# Connector_LV.net
KiCad netlist of a schematic drawn in Altium Designer
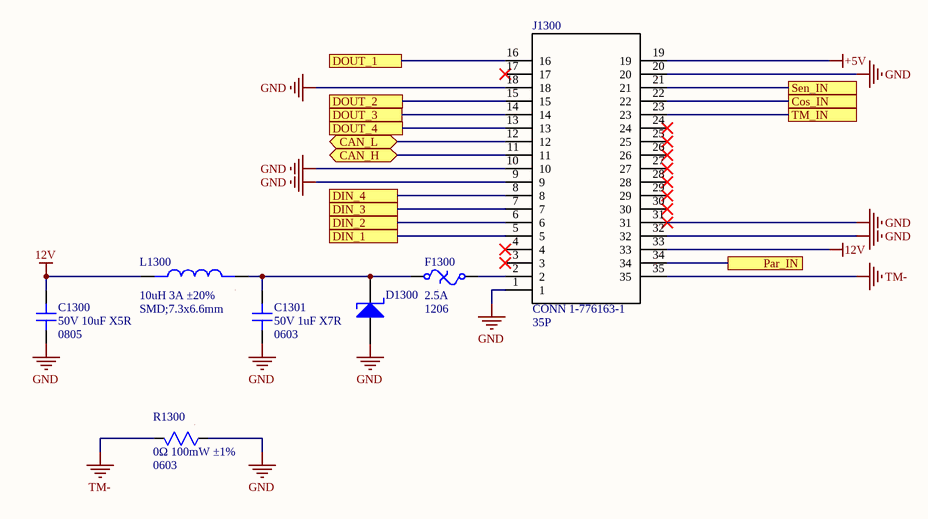
[diagram p0: Connector_LV.SchDoc]

(export (version "E")
  (design (tool "Eeschema 10.0.6"))
  (components
    (comp (ref "C1300")
      (value "50V 10uF X5R")
      (footprint "CAP SMD 0805")
      (description "Condensadores de cerámica multicapa (MLCC- SMD/SMT) 10 uF 50 VDC 10% 0805 X5R")
      (fields
        (field (name "PACKAGE") "0805")
        (field (name "MPN") "GRM21BR61H106KE43K")
        (field (name "MANUFACTURER") "muRata")
      )
      (libsource (lib "eUSR_Database") (part "CAP non polarized"))
    )
    (comp (ref "C1301")
      (value "50V 1uF X7R")
      (footprint "CAP SMD 0603")
      (description "Condensadores de cerámica multicapa (MLCC- SMD/SMT) WCAP-CSGP 1uF 50 Vol 10%")
      (fields
        (field (name "PACKAGE") "0603")
        (field (name "MPN") "885012206126")
        (field (name "MANUFACTURER") "Wurth Elektronik")
      )
      (libsource (lib "eUSR_Database") (part "CAP non polarized"))
    )
    (comp (ref "D1300")
      (value "DIODE SCHOTTKY")
      (footprint "DO-214AB")
      (description "Diodos y rectificadores Schottky 3A 60V")
      (fields (field (name "MPN") "MBRS360T3G") (field (name "MANUFACTURER") "onsemi"))
      (libsource (lib "eUSR_Database") (part "DIODE SCHOTTKY"))
    )
    (comp (ref "F1300")
      (value "2.5A")
      (footprint "FUSE SMD 1206")
      (description "Fusibles de montaje en superficie 2.5A Fast Acting 1206 SinglFuse")
      (fields
        (field (name "PACKAGE") "1206")
        (field (name "MPN") "SF-1206F250-2")
        (field (name "MANUFACTURER") "Bourns")
      )
      (libsource (lib "eUSR_Database") (part "FUSE"))
    )
    (comp (ref "J1300")
      (value "CONN 1-776163-1")
      (footprint "1-776163-1")
      (description "Conectores para automoción 35P HEADER AMPSEAL ASSEMBLY")
      (fields
        (field (name "ALTIUM_VALUE") "35P")
        (field (name "MPN") "1-776163-1")
        (field (name "MANUFACTURER") "TE Connectivity")
      )
      (libsource (lib "eUSR_Database") (part "CONN 1-776163-1"))
    )
    (comp (ref "L1300")
      (value "10uH 3A ±20%")
      (footprint "IND SMD 7.3x6.6")
      (description "Inductores de potencia (SMD) WE-LHMI Powr SMD7030 10uH 3.0A 85mOhm")
      (fields
        (field (name "PACKAGE") "SMD;7.3x6.6mm")
        (field (name "MPN") "74437346100")
        (field (name "MANUFACTURER") "Wurth Elektronik")
      )
      (libsource (lib "eUSR_Database") (part "IND"))
    )
    (comp (ref "R1300")
      (value "0Ω 100mW ±1%")
      (footprint "RES SMD 0603")
      (description "Resistores de película gruesa - SMD WRIS-RSKS <0.05 Ohms 0.1 W Jumper 0603 AEC-Q200")
      (fields
        (field (name "PACKAGE") "0603")
        (field (name "MPN") "560112116001")
        (field (name "MANUFACTURER") "Wurth Elektronik")
      )
      (libsource (lib "eUSR_Database") (part "RES"))
    )
  )
  (nets
    (net (code "1") (name "+5V") (class "Default")
      (node (ref "J1300") (pin "19") (pinfunction "19_19") (pintype "passive"))
    )
    (net (code "2") (name "/CAN_H") (class "Default")
      (node (ref "J1300") (pin "11") (pinfunction "11_11") (pintype "passive"))
    )
    (net (code "3") (name "/CAN_L") (class "Default")
      (node (ref "J1300") (pin "12") (pinfunction "12_12") (pintype "passive"))
    )
    (net (code "4") (name "/Cos_IN") (class "Default")
      (node (ref "J1300") (pin "22") (pinfunction "22_22") (pintype "passive"))
    )
    (net (code "5") (name "/DIN_1") (class "Default")
      (node (ref "J1300") (pin "5") (pinfunction "5_5") (pintype "passive"))
    )
    (net (code "6") (name "/DIN_2") (class "Default")
      (node (ref "J1300") (pin "6") (pinfunction "6_6") (pintype "passive"))
    )
    (net (code "7") (name "/DIN_3") (class "Default")
      (node (ref "J1300") (pin "7") (pinfunction "7_7") (pintype "passive"))
    )
    (net (code "8") (name "/DIN_4") (class "Default")
      (node (ref "J1300") (pin "8") (pinfunction "8_8") (pintype "passive"))
    )
    (net (code "9") (name "/DOUT_1") (class "Default")
      (node (ref "J1300") (pin "16") (pinfunction "16_16") (pintype "passive"))
    )
    (net (code "10") (name "/DOUT_2") (class "Default")
      (node (ref "J1300") (pin "15") (pinfunction "15_15") (pintype "passive"))
    )
    (net (code "11") (name "/DOUT_3") (class "Default")
      (node (ref "J1300") (pin "14") (pinfunction "14_14") (pintype "passive"))
    )
    (net (code "12") (name "/DOUT_4") (class "Default")
      (node (ref "J1300") (pin "13") (pinfunction "13_13") (pintype "passive"))
    )
    (net (code "13") (name "/Par_IN") (class "Default")
      (node (ref "J1300") (pin "34") (pinfunction "34_34") (pintype "passive"))
    )
    (net (code "14") (name "/Sen_IN") (class "Default")
      (node (ref "J1300") (pin "21") (pinfunction "21_21") (pintype "passive"))
    )
    (net (code "15") (name "/TM_IN") (class "Default")
      (node (ref "J1300") (pin "23") (pinfunction "23_23") (pintype "passive"))
    )
    (net (code "16") (name "12V") (class "Default")
      (node (ref "C1300") (pin "1") (pinfunction "1_1") (pintype "passive"))
      (node (ref "J1300") (pin "33") (pinfunction "33_33") (pintype "passive"))
      (node (ref "L1300") (pin "1") (pinfunction "1_1") (pintype "passive"))
    )
    (net (code "17") (name "GND") (class "Default")
      (node (ref "C1300") (pin "2") (pinfunction "2_2") (pintype "passive"))
      (node (ref "C1301") (pin "2") (pinfunction "2_2") (pintype "passive"))
      (node (ref "D1300") (pin "A") (pinfunction "A_A") (pintype "passive"))
      (node (ref "J1300") (pin "1") (pinfunction "1_1") (pintype "passive"))
      (node (ref "J1300") (pin "10") (pinfunction "10_10") (pintype "passive"))
      (node (ref "J1300") (pin "18") (pinfunction "18_18") (pintype "passive"))
      (node (ref "J1300") (pin "20") (pinfunction "20_20") (pintype "passive"))
      (node (ref "J1300") (pin "31") (pinfunction "31_31") (pintype "passive"))
      (node (ref "J1300") (pin "32") (pinfunction "32_32") (pintype "passive"))
      (node (ref "J1300") (pin "9") (pinfunction "9_9") (pintype "passive"))
      (node (ref "R1300") (pin "1") (pinfunction "1_1") (pintype "passive"))
    )
    (net (code "18") (name "Net-(C1301-Pad1)") (class "Default")
      (node (ref "C1301") (pin "1") (pinfunction "1_1") (pintype "passive"))
      (node (ref "D1300") (pin "K") (pinfunction "K_K") (pintype "passive"))
      (node (ref "F1300") (pin "1") (pinfunction "1_1") (pintype "passive"))
      (node (ref "L1300") (pin "2") (pinfunction "2_2") (pintype "passive"))
    )
    (net (code "19") (name "Net-(F1300-Pad2)") (class "Default")
      (node (ref "F1300") (pin "2") (pinfunction "2_2") (pintype "passive"))
      (node (ref "J1300") (pin "2") (pinfunction "2_2") (pintype "passive"))
    )
    (net (code "20") (name "TM-") (class "Default")
      (node (ref "J1300") (pin "35") (pinfunction "35_35") (pintype "passive"))
      (node (ref "R1300") (pin "2") (pinfunction "2_2") (pintype "passive"))
    )
    (net (code "21") (name "unconnected-(J1300-Pad3)") (class "Default")
      (node (ref "J1300") (pin "3") (pinfunction "3_3") (pintype "passive+no_connect"))
    )
    (net (code "22") (name "unconnected-(J1300-Pad4)") (class "Default")
      (node (ref "J1300") (pin "4") (pinfunction "4_4") (pintype "passive+no_connect"))
    )
    (net (code "23") (name "unconnected-(J1300-Pad17)") (class "Default")
      (node (ref "J1300") (pin "17") (pinfunction "17_17") (pintype "passive+no_connect"))
    )
    (net (code "24") (name "unconnected-(J1300-Pad24)") (class "Default")
      (node (ref "J1300") (pin "24") (pinfunction "24_24") (pintype "passive+no_connect"))
    )
    (net (code "25") (name "unconnected-(J1300-Pad25)") (class "Default")
      (node (ref "J1300") (pin "25") (pinfunction "25_25") (pintype "passive+no_connect"))
    )
    (net (code "26") (name "unconnected-(J1300-Pad26)") (class "Default")
      (node (ref "J1300") (pin "26") (pinfunction "26_26") (pintype "passive+no_connect"))
    )
    (net (code "27") (name "unconnected-(J1300-Pad27)") (class "Default")
      (node (ref "J1300") (pin "27") (pinfunction "27_27") (pintype "passive+no_connect"))
    )
    (net (code "28") (name "unconnected-(J1300-Pad28)") (class "Default")
      (node (ref "J1300") (pin "28") (pinfunction "28_28") (pintype "passive+no_connect"))
    )
    (net (code "29") (name "unconnected-(J1300-Pad29)") (class "Default")
      (node (ref "J1300") (pin "29") (pinfunction "29_29") (pintype "passive+no_connect"))
    )
    (net (code "30") (name "unconnected-(J1300-Pad30)") (class "Default")
      (node (ref "J1300") (pin "30") (pinfunction "30_30") (pintype "passive+no_connect"))
    )
  )
)
